# HV_amplifier.net
KiCad netlist of a schematic drawn in Altium Designer
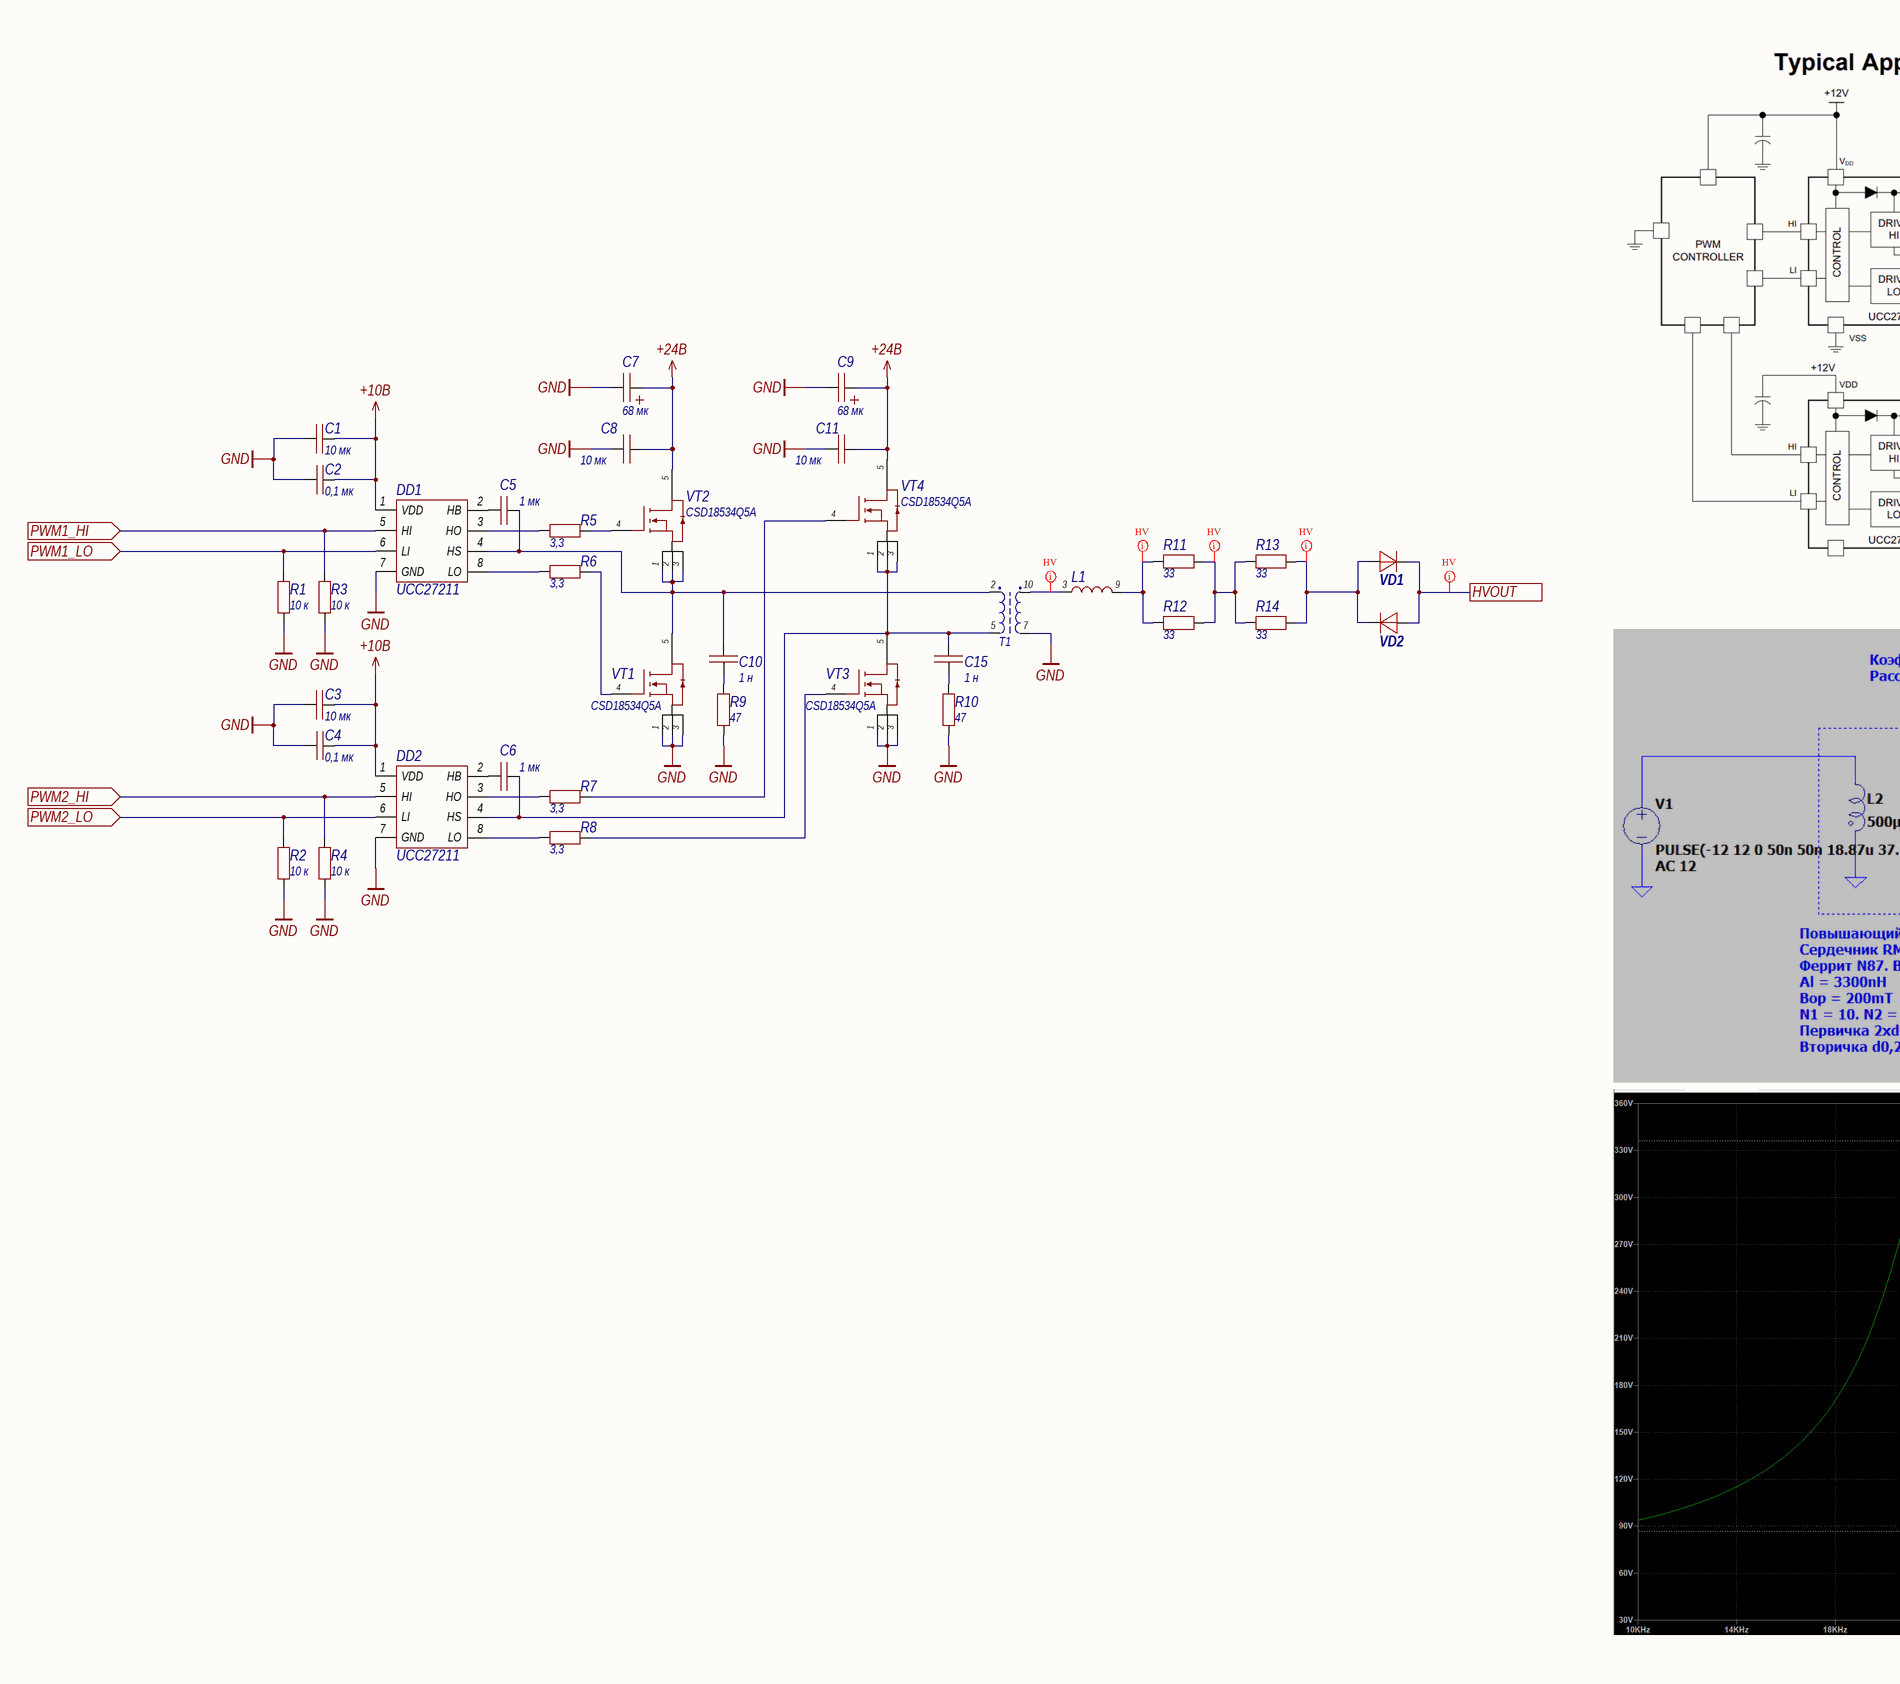
[diagram p0: HV_amplifier.SchDoc, left]
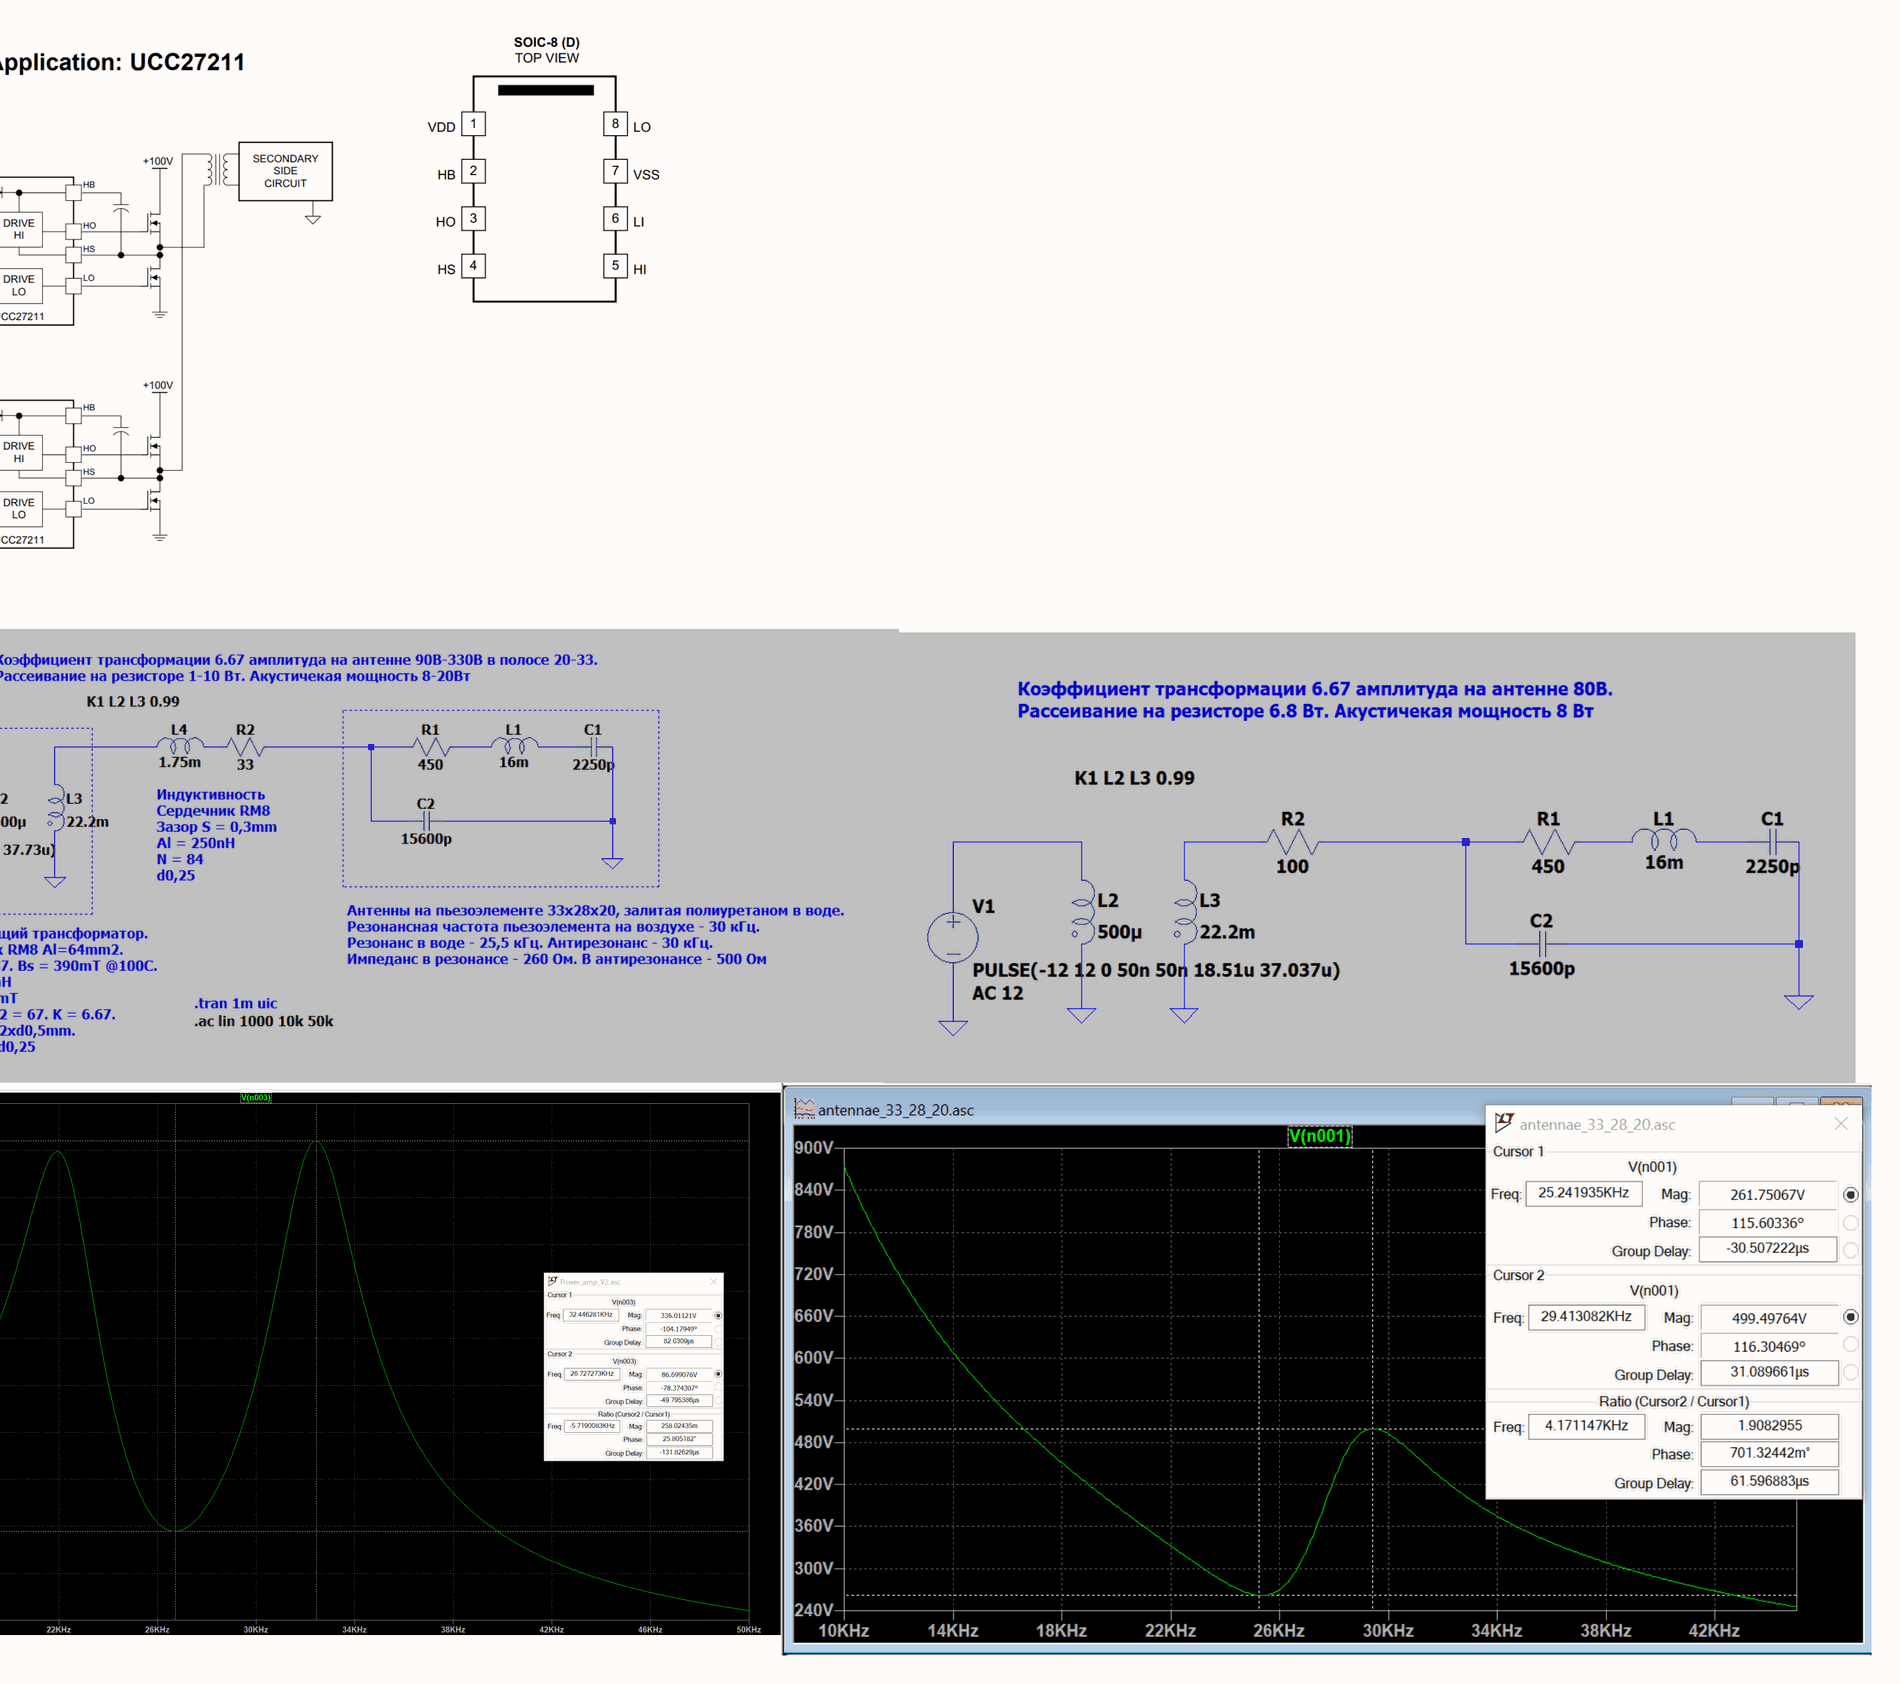
[diagram p1: HV_amplifier.SchDoc, right]

(export (version "E")
  (design (tool "Eeschema 10.0.6"))
  (components
    (comp (ref "C1")
      (value "10 мк")
      (footprint "1210C")
      (description "Конденсатор 1210C ёмкостью 10 мк 10%, 35 В, X7R")
      (fields (field (name "PART NUMBER") "Capacitor_10u_10_35V_X7R_1210C") (field (name "TOLERANCE") "10%"))
      (libsource (lib "Hydrolib") (part "Capacitor"))
    )
    (comp (ref "C2")
      (value "0,1 мк")
      (footprint "0603C")
      (description "Конденсатор 0603C ёмкостью 0,1 мк 10%, 50 В, X7R")
      (fields (field (name "PART NUMBER") "Capacitor_0,1u_10_50V_X7R_0603C") (field (name "TOLERANCE") "10%"))
      (libsource (lib "Hydrolib") (part "Capacitor"))
    )
    (comp (ref "C3")
      (value "10 мк")
      (footprint "1210C")
      (description "Конденсатор 1210C ёмкостью 10 мк 10%, 35 В, X7R")
      (fields (field (name "PART NUMBER") "Capacitor_10u_10_35V_X7R_1210C") (field (name "TOLERANCE") "10%"))
      (libsource (lib "Hydrolib") (part "Capacitor"))
    )
    (comp (ref "C4")
      (value "0,1 мк")
      (footprint "0603C")
      (description "Конденсатор 0603C ёмкостью 0,1 мк 10%, 50 В, X7R")
      (fields (field (name "PART NUMBER") "Capacitor_0,1u_10_50V_X7R_0603C") (field (name "TOLERANCE") "10%"))
      (libsource (lib "Hydrolib") (part "Capacitor"))
    )
    (comp (ref "C5")
      (value "1 мк")
      (footprint "0603C")
      (description "Конденсатор 0603C ёмкостью 1 мк 10%, 25 В, X7R")
      (fields (field (name "PART NUMBER") "Capacitor_1u_10_25V_X7R_0603C") (field (name "TOLERANCE") "10%"))
      (libsource (lib "Hydrolib") (part "Capacitor"))
    )
    (comp (ref "C6")
      (value "1 мк")
      (footprint "0603C")
      (description "Конденсатор 0603C ёмкостью 1 мк 10%, 25 В, X7R")
      (fields (field (name "PART NUMBER") "Capacitor_1u_10_25V_X7R_0603C") (field (name "TOLERANCE") "10%"))
      (libsource (lib "Hydrolib") (part "Capacitor"))
    )
    (comp (ref "C7")
      (value "68 мк")
      (footprint "CAP_SMD_10x12,7")
      (fields
        (field (name "PART NUMBER") "50SVPF68M")
        (field (name "TOLERANCE") "20")
        (field (name "Comment") "Capacitor")
        (field (name "АВТОР") "glebmih")
      )
      (libsource (lib "Hydrolib") (part "Capacitor_polar"))
    )
    (comp (ref "C8")
      (value "10 мк")
      (footprint "1210C")
      (description "Конденсатор 1210C ёмкостью 10 мк 10%, 35 В, X7R")
      (fields (field (name "PART NUMBER") "Capacitor_10u_10_35V_X7R_1210C") (field (name "TOLERANCE") "10%"))
      (libsource (lib "Hydrolib") (part "Capacitor"))
    )
    (comp (ref "C9")
      (value "68 мк")
      (footprint "CAP_SMD_10x12,7")
      (fields
        (field (name "PART NUMBER") "50SVPF68M")
        (field (name "TOLERANCE") "20")
        (field (name "Comment") "Capacitor")
        (field (name "АВТОР") "glebmih")
      )
      (libsource (lib "Hydrolib") (part "Capacitor_polar"))
    )
    (comp (ref "C10")
      (value "1 н")
      (footprint "0603C")
      (description "Конденсатор 0603C ёмкостью 1 н 5%, 50 В, NP0")
      (fields
        (field (name "PART NUMBER") "Capacitor_1n_5_50V_NP0_0603C")
        (field (name "TOLERANCE") "5%")
        (field (name "АВТОР") "glebmih")
      )
      (libsource (lib "Hydrolib") (part "Capacitor"))
    )
    (comp (ref "C11")
      (value "10 мк")
      (footprint "1210C")
      (description "Конденсатор 1210C ёмкостью 10 мк 10%, 35 В, X7R")
      (fields (field (name "PART NUMBER") "Capacitor_10u_10_35V_X7R_1210C") (field (name "TOLERANCE") "10%"))
      (libsource (lib "Hydrolib") (part "Capacitor"))
    )
    (comp (ref "C15")
      (value "1 н")
      (footprint "0603C")
      (description "Конденсатор 0603C ёмкостью 1 н 5%, 50 В, NP0")
      (fields
        (field (name "PART NUMBER") "Capacitor_1n_5_50V_NP0_0603C")
        (field (name "TOLERANCE") "5%")
        (field (name "АВТОР") "glebmih")
      )
      (libsource (lib "Hydrolib") (part "Capacitor"))
    )
    (comp (ref "DD1")
      (value "UCC27211")
      (footprint "SOIC-8")
      (description "Полумостовой драйвер затвора для mosfet транзисторов")
      (fields (field (name "АВТОР") "glebmih"))
      (libsource (lib "Hydrolib") (part "UCC27211"))
    )
    (comp (ref "DD2")
      (value "UCC27211")
      (footprint "SOIC-8")
      (description "Полумостовой драйвер затвора для mosfet транзисторов")
      (fields (field (name "АВТОР") "glebmih"))
      (libsource (lib "Hydrolib") (part "UCC27211"))
    )
    (comp (ref "L1")
      (value "Inductance_RM8")
      (footprint "RM8_trans")
      (description "Индуктивность на сердечнике RM8")
      (fields (field (name "АВТОР") "glebmih"))
      (libsource (lib "Hydrolib") (part "Inductance_RM8"))
    )
    (comp (ref "R1")
      (value "10 к")
      (footprint "0603R")
      (description "Резистор номиналом 10 кОм 1%")
      (fields (field (name "PART NUMBER") "Resistor_10k_1_0603") (field (name "TOLERANCE") "1%"))
      (libsource (lib "") (part "Resistor_1"))
    )
    (comp (ref "R2")
      (value "10 к")
      (footprint "0603R")
      (description "Резистор номиналом 10 кОм 1%")
      (fields (field (name "PART NUMBER") "Resistor_10k_1_0603") (field (name "TOLERANCE") "1%"))
      (libsource (lib "") (part "Resistor_1"))
    )
    (comp (ref "R3")
      (value "10 к")
      (footprint "0603R")
      (description "Резистор номиналом 10 кОм 1%")
      (fields (field (name "PART NUMBER") "Resistor_10k_1_0603") (field (name "TOLERANCE") "1%"))
      (libsource (lib "") (part "Resistor_1"))
    )
    (comp (ref "R4")
      (value "10 к")
      (footprint "0603R")
      (description "Резистор номиналом 10 кОм 1%")
      (fields (field (name "PART NUMBER") "Resistor_10k_1_0603") (field (name "TOLERANCE") "1%"))
      (libsource (lib "") (part "Resistor_1"))
    )
    (comp (ref "R5")
      (value "3,3")
      (footprint "0603R")
      (description "Резистор номиналом 3,3 Ом 1%")
      (fields (field (name "PART NUMBER") "Resistor_3.3_1_0603") (field (name "TOLERANCE") "1%"))
      (libsource (lib "Hydrolib") (part "Resistor"))
    )
    (comp (ref "R6")
      (value "3,3")
      (footprint "0603R")
      (description "Резистор номиналом 3,3 Ом 1%")
      (fields (field (name "PART NUMBER") "Resistor_3.3_1_0603") (field (name "TOLERANCE") "1%"))
      (libsource (lib "Hydrolib") (part "Resistor"))
    )
    (comp (ref "R7")
      (value "3,3")
      (footprint "0603R")
      (description "Резистор номиналом 3,3 Ом 1%")
      (fields (field (name "PART NUMBER") "Resistor_3.3_1_0603") (field (name "TOLERANCE") "1%"))
      (libsource (lib "Hydrolib") (part "Resistor"))
    )
    (comp (ref "R8")
      (value "3,3")
      (footprint "0603R")
      (description "Резистор номиналом 3,3 Ом 1%")
      (fields (field (name "PART NUMBER") "Resistor_3.3_1_0603") (field (name "TOLERANCE") "1%"))
      (libsource (lib "Hydrolib") (part "Resistor"))
    )
    (comp (ref "R9")
      (value "47")
      (footprint "0805R")
      (description "Резистор номиналом 47 Ом 1%")
      (fields
        (field (name "PART NUMBER") "Resistor_47_1_0805")
        (field (name "TOLERANCE") "1%")
        (field (name "АВТОР") "glebmih")
      )
      (libsource (lib "") (part "Resistor_1"))
    )
    (comp (ref "R10")
      (value "47")
      (footprint "0805R")
      (description "Резистор номиналом 47 Ом 1%")
      (fields
        (field (name "PART NUMBER") "Resistor_47_1_0805")
        (field (name "TOLERANCE") "1%")
        (field (name "АВТОР") "glebmih")
      )
      (libsource (lib "") (part "Resistor_1"))
    )
    (comp (ref "R11")
      (value "33")
      (footprint "2512R")
      (description "Резистор номиналом 33 Ом 1%")
      (fields
        (field (name "PART NUMBER") "Resistor_33_1_2512")
        (field (name "TOLERANCE") "1%")
        (field (name "АВТОР") "glebmih")
      )
      (libsource (lib "Hydrolib") (part "Resistor"))
    )
    (comp (ref "R12")
      (value "33")
      (footprint "2512R")
      (description "Резистор номиналом 33 Ом 1%")
      (fields
        (field (name "PART NUMBER") "Resistor_33_1_2512")
        (field (name "TOLERANCE") "1%")
        (field (name "АВТОР") "glebmih")
      )
      (libsource (lib "Hydrolib") (part "Resistor"))
    )
    (comp (ref "R13")
      (value "33")
      (footprint "2512R")
      (description "Резистор номиналом 33 Ом 1%")
      (fields
        (field (name "PART NUMBER") "Resistor_33_1_2512")
        (field (name "TOLERANCE") "1%")
        (field (name "АВТОР") "glebmih")
      )
      (libsource (lib "Hydrolib") (part "Resistor"))
    )
    (comp (ref "R14")
      (value "33")
      (footprint "2512R")
      (description "Резистор номиналом 33 Ом 1%")
      (fields
        (field (name "PART NUMBER") "Resistor_33_1_2512")
        (field (name "TOLERANCE") "1%")
        (field (name "АВТОР") "glebmih")
      )
      (libsource (lib "Hydrolib") (part "Resistor"))
    )
    (comp (ref "T1")
      (value "Transformer_RM8")
      (footprint "RM8_trans")
      (description "Трансформатор на сердечнике RM8")
      (fields (field (name "АВТОР") "glebmih"))
      (libsource (lib "Hydrolib") (part "Transformer_RM8"))
    )
    (comp (ref "VD1")
      (value "SMA4007")
      (footprint "SMA")
      (description "Выпрямительный диод на 1000 В, ном. ток 1 А А")
      (fields (field (name "АВТОР") "glebmih"))
      (libsource (lib "Hydrolib") (part "Rectifier_diode"))
    )
    (comp (ref "VD2")
      (value "SMA4007")
      (footprint "SMA")
      (description "Выпрямительный диод на 1000 В, ном. ток 1 А А")
      (fields (field (name "АВТОР") "glebmih"))
      (libsource (lib "Hydrolib") (part "Rectifier_diode"))
    )
    (comp (ref "VT1")
      (value "CSD18534Q5A")
      (footprint "SON-8_5x6")
      (description "N-канальный MOSFET, 60 В, 50 А")
      (fields (field (name "АВТОР") "glebmih"))
      (libsource (lib "Hydrolib") (part "MOSFET_N-channel_5pin"))
    )
    (comp (ref "VT2")
      (value "CSD18534Q5A")
      (footprint "SON-8_5x6")
      (description "N-канальный MOSFET, 60 В, 50 А")
      (fields (field (name "АВТОР") "glebmih"))
      (libsource (lib "Hydrolib") (part "MOSFET_N-channel_5pin"))
    )
    (comp (ref "VT3")
      (value "CSD18534Q5A")
      (footprint "SON-8_5x6")
      (description "N-канальный MOSFET, 60 В, 50 А")
      (fields (field (name "АВТОР") "glebmih"))
      (libsource (lib "Hydrolib") (part "MOSFET_N-channel_5pin"))
    )
    (comp (ref "VT4")
      (value "CSD18534Q5A")
      (footprint "SON-8_5x6")
      (description "N-канальный MOSFET, 60 В, 50 А")
      (fields (field (name "АВТОР") "glebmih"))
      (libsource (lib "Hydrolib") (part "MOSFET_N-channel_5pin"))
    )
  )
  (nets
    (net (code "1") (name "+10В") (class "Default")
      (node (ref "C1") (pin "1") (pinfunction "1_1") (pintype "passive"))
      (node (ref "C2") (pin "2") (pinfunction "2_2") (pintype "passive"))
      (node (ref "C3") (pin "1") (pinfunction "1_1") (pintype "passive"))
      (node (ref "C4") (pin "2") (pinfunction "2_2") (pintype "passive"))
      (node (ref "DD1") (pin "1") (pinfunction "VDD_1") (pintype "passive"))
      (node (ref "DD2") (pin "1") (pinfunction "VDD_1") (pintype "passive"))
    )
    (net (code "2") (name "+24В") (class "Default")
      (node (ref "C11") (pin "2") (pinfunction "2_2") (pintype "passive"))
      (node (ref "C7") (pin "1") (pinfunction "1_1") (pintype "passive"))
      (node (ref "C8") (pin "2") (pinfunction "2_2") (pintype "passive"))
      (node (ref "C9") (pin "1") (pinfunction "1_1") (pintype "passive"))
      (node (ref "VT2") (pin "5") (pinfunction "5_5") (pintype "passive"))
      (node (ref "VT4") (pin "5") (pinfunction "5_5") (pintype "passive"))
    )
    (net (code "3") (name "/HVOUT") (class "Default")
      (node (ref "VD1") (pin "2") (pinfunction "2_2") (pintype "passive"))
      (node (ref "VD2") (pin "1") (pinfunction "1_1") (pintype "passive"))
    )
    (net (code "4") (name "/PWM1_HI") (class "Default")
      (node (ref "DD1") (pin "5") (pinfunction "HI_5") (pintype "passive"))
      (node (ref "R3") (pin "2") (pinfunction "2_2") (pintype "passive"))
    )
    (net (code "5") (name "/PWM1_LO") (class "Default")
      (node (ref "DD1") (pin "6") (pinfunction "LI_6") (pintype "passive"))
      (node (ref "R1") (pin "2") (pinfunction "2_2") (pintype "passive"))
    )
    (net (code "6") (name "/PWM2_HI") (class "Default")
      (node (ref "DD2") (pin "5") (pinfunction "HI_5") (pintype "passive"))
      (node (ref "R4") (pin "2") (pinfunction "2_2") (pintype "passive"))
    )
    (net (code "7") (name "/PWM2_LO") (class "Default")
      (node (ref "DD2") (pin "6") (pinfunction "LI_6") (pintype "passive"))
      (node (ref "R2") (pin "2") (pinfunction "2_2") (pintype "passive"))
    )
    (net (code "8") (name "GND") (class "Default")
      (node (ref "C1") (pin "2") (pinfunction "2_2") (pintype "passive"))
      (node (ref "C11") (pin "1") (pinfunction "1_1") (pintype "passive"))
      (node (ref "C2") (pin "1") (pinfunction "1_1") (pintype "passive"))
      (node (ref "C3") (pin "2") (pinfunction "2_2") (pintype "passive"))
      (node (ref "C4") (pin "1") (pinfunction "1_1") (pintype "passive"))
      (node (ref "C7") (pin "2") (pinfunction "2_2") (pintype "passive"))
      (node (ref "C8") (pin "1") (pinfunction "1_1") (pintype "passive"))
      (node (ref "C9") (pin "2") (pinfunction "2_2") (pintype "passive"))
      (node (ref "DD1") (pin "7") (pinfunction "GND_7") (pintype "passive"))
      (node (ref "DD2") (pin "7") (pinfunction "GND_7") (pintype "passive"))
      (node (ref "R1") (pin "1") (pinfunction "1_1") (pintype "passive"))
      (node (ref "R10") (pin "1") (pinfunction "1_1") (pintype "passive"))
      (node (ref "R2") (pin "1") (pinfunction "1_1") (pintype "passive"))
      (node (ref "R3") (pin "1") (pinfunction "1_1") (pintype "passive"))
      (node (ref "R4") (pin "1") (pinfunction "1_1") (pintype "passive"))
      (node (ref "R9") (pin "1") (pinfunction "1_1") (pintype "passive"))
      (node (ref "T1") (pin "7") (pinfunction "4_7") (pintype "passive"))
      (node (ref "VT1") (pin "1") (pinfunction "1_1") (pintype "passive"))
      (node (ref "VT1") (pin "2") (pinfunction "2_2") (pintype "passive"))
      (node (ref "VT1") (pin "3") (pinfunction "3_3") (pintype "passive"))
      (node (ref "VT3") (pin "1") (pinfunction "1_1") (pintype "passive"))
      (node (ref "VT3") (pin "2") (pinfunction "2_2") (pintype "passive"))
      (node (ref "VT3") (pin "3") (pinfunction "3_3") (pintype "passive"))
    )
    (net (code "9") (name "Net-(C10-Pad1)") (class "Default")
      (node (ref "C10") (pin "1") (pinfunction "1_1") (pintype "passive"))
      (node (ref "R9") (pin "2") (pinfunction "2_2") (pintype "passive"))
    )
    (net (code "10") (name "Net-(C15-Pad1)") (class "Default")
      (node (ref "C15") (pin "1") (pinfunction "1_1") (pintype "passive"))
      (node (ref "R10") (pin "2") (pinfunction "2_2") (pintype "passive"))
    )
    (net (code "11") (name "Net-(DD1-HB)") (class "Default")
      (node (ref "C5") (pin "1") (pinfunction "1_1") (pintype "passive"))
      (node (ref "DD1") (pin "2") (pinfunction "HB_2") (pintype "passive"))
    )
    (net (code "12") (name "Net-(DD1-HO)") (class "Default")
      (node (ref "DD1") (pin "3") (pinfunction "HO_3") (pintype "passive"))
      (node (ref "R5") (pin "1") (pinfunction "1_1") (pintype "passive"))
    )
    (net (code "13") (name "Net-(DD1-HS)") (class "Default")
      (node (ref "C10") (pin "2") (pinfunction "2_2") (pintype "passive"))
      (node (ref "C5") (pin "2") (pinfunction "2_2") (pintype "passive"))
      (node (ref "DD1") (pin "4") (pinfunction "HS_4") (pintype "passive"))
      (node (ref "T1") (pin "2") (pinfunction "2_2") (pintype "passive"))
      (node (ref "VT1") (pin "5") (pinfunction "5_5") (pintype "passive"))
      (node (ref "VT2") (pin "1") (pinfunction "1_1") (pintype "passive"))
      (node (ref "VT2") (pin "2") (pinfunction "2_2") (pintype "passive"))
      (node (ref "VT2") (pin "3") (pinfunction "3_3") (pintype "passive"))
    )
    (net (code "14") (name "Net-(DD1-LO)") (class "Default")
      (node (ref "DD1") (pin "8") (pinfunction "LO_8") (pintype "passive"))
      (node (ref "R6") (pin "1") (pinfunction "1_1") (pintype "passive"))
    )
    (net (code "15") (name "Net-(DD2-HB)") (class "Default")
      (node (ref "C6") (pin "1") (pinfunction "1_1") (pintype "passive"))
      (node (ref "DD2") (pin "2") (pinfunction "HB_2") (pintype "passive"))
    )
    (net (code "16") (name "Net-(DD2-HO)") (class "Default")
      (node (ref "DD2") (pin "3") (pinfunction "HO_3") (pintype "passive"))
      (node (ref "R7") (pin "1") (pinfunction "1_1") (pintype "passive"))
    )
    (net (code "17") (name "Net-(DD2-HS)") (class "Default")
      (node (ref "C15") (pin "2") (pinfunction "2_2") (pintype "passive"))
      (node (ref "C6") (pin "2") (pinfunction "2_2") (pintype "passive"))
      (node (ref "DD2") (pin "4") (pinfunction "HS_4") (pintype "passive"))
      (node (ref "T1") (pin "5") (pinfunction "5_5") (pintype "passive"))
      (node (ref "VT3") (pin "5") (pinfunction "5_5") (pintype "passive"))
      (node (ref "VT4") (pin "1") (pinfunction "1_1") (pintype "passive"))
      (node (ref "VT4") (pin "2") (pinfunction "2_2") (pintype "passive"))
      (node (ref "VT4") (pin "3") (pinfunction "3_3") (pintype "passive"))
    )
    (net (code "18") (name "Net-(DD2-LO)") (class "Default")
      (node (ref "DD2") (pin "8") (pinfunction "LO_8") (pintype "passive"))
      (node (ref "R8") (pin "1") (pinfunction "1_1") (pintype "passive"))
    )
    (net (code "19") (name "Net-(L1-Pad9)") (class "Default")
      (node (ref "L1") (pin "9") (pinfunction "9_9") (pintype "passive"))
      (node (ref "R11") (pin "1") (pinfunction "1_1") (pintype "passive"))
      (node (ref "R12") (pin "1") (pinfunction "1_1") (pintype "passive"))
    )
    (net (code "20") (name "Net-(R5-Pad2)") (class "Default")
      (node (ref "R5") (pin "2") (pinfunction "2_2") (pintype "passive"))
      (node (ref "VT2") (pin "4") (pinfunction "4_4") (pintype "passive"))
    )
    (net (code "21") (name "Net-(R6-Pad2)") (class "Default")
      (node (ref "R6") (pin "2") (pinfunction "2_2") (pintype "passive"))
      (node (ref "VT1") (pin "4") (pinfunction "4_4") (pintype "passive"))
    )
    (net (code "22") (name "Net-(R7-Pad2)") (class "Default")
      (node (ref "R7") (pin "2") (pinfunction "2_2") (pintype "passive"))
      (node (ref "VT4") (pin "4") (pinfunction "4_4") (pintype "passive"))
    )
    (net (code "23") (name "Net-(R8-Pad2)") (class "Default")
      (node (ref "R8") (pin "2") (pinfunction "2_2") (pintype "passive"))
      (node (ref "VT3") (pin "4") (pinfunction "4_4") (pintype "passive"))
    )
    (net (code "24") (name "Net-(R11-Pad2)") (class "Default")
      (node (ref "R11") (pin "2") (pinfunction "2_2") (pintype "passive"))
      (node (ref "R12") (pin "2") (pinfunction "2_2") (pintype "passive"))
      (node (ref "R13") (pin "1") (pinfunction "1_1") (pintype "passive"))
      (node (ref "R14") (pin "1") (pinfunction "1_1") (pintype "passive"))
    )
    (net (code "25") (name "Net-(R13-Pad2)") (class "Default")
      (node (ref "R13") (pin "2") (pinfunction "2_2") (pintype "passive"))
      (node (ref "R14") (pin "2") (pinfunction "2_2") (pintype "passive"))
      (node (ref "VD1") (pin "1") (pinfunction "1_1") (pintype "passive"))
      (node (ref "VD2") (pin "2") (pinfunction "2_2") (pintype "passive"))
    )
    (net (code "26") (name "Net-(T1-3)") (class "Default")
      (node (ref "L1") (pin "3") (pinfunction "3_3") (pintype "passive"))
      (node (ref "T1") (pin "10") (pinfunction "3_10") (pintype "passive"))
    )
  )
)
